# HDMI.net
KiCad netlist of a schematic drawn in Altium Designer
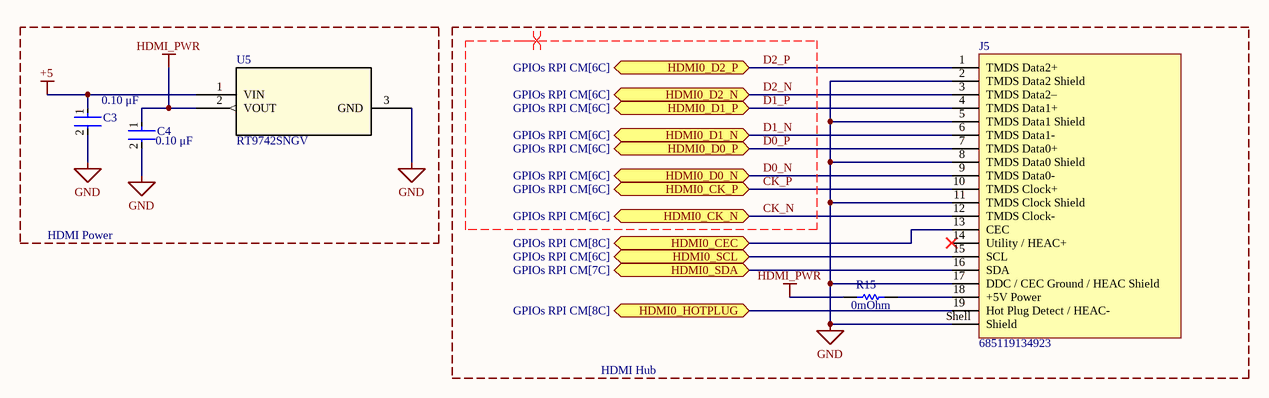
[diagram p0: HDMI.SchDoc]

(export (version "E")
  (design (tool "Eeschema 10.0.6"))
  (components
    (comp (ref "C3")
      (value "C0402C104K8PACTU")
      (footprint "FP-C0402-BB-MFG")
      (description "CAP CER 0.1UF 10V X5R 0402")
      (fields
        (field (name "CAPACITANCE") "0.10 μF")
        (field (name "MANUFACTURER") "Kemet")
        (field (name "TOLERANCE") "0.1")
      )
      (libsource (lib "Altium Content Vault") (part "b4654b650e69147ec39a6b967a45e02"))
    )
    (comp (ref "C4")
      (value "C0402C104K8PACTU")
      (footprint "FP-C0402-BB-MFG")
      (description "CAP CER 0.1UF 10V X5R 0402")
      (fields
        (field (name "CAPACITANCE") "0.10 μF")
        (field (name "MANUFACTURER") "Kemet")
        (field (name "TOLERANCE") "0.1")
      )
      (libsource (lib "Altium Content Vault") (part "b4654b650e69147ec39a6b967a45e02"))
    )
    (comp (ref "J5")
      (value "685119134923")
      (footprint "685119134923")
      (libsource (lib "Altium Content Vault") (part "HDMI_Type A"))
    )
    (comp (ref "R15")
      (value "ERJ2GE0R00X")
      (footprint "RESC1005X40X25LL05T05")
      (description "Chip Resistor, 0 Ohm, 0.1 W, -55 to 155 degC, 0402 (1005 Metric), RoHS, Tape and Reel")
      (fields
        (field (name "MANUFACTURER") "Panasonic")
        (field (name "RESISTANCE") "0mOhm")
        (field (name "TOLERANCE") "5%")
      )
      (libsource (lib "Altium Content Vault") (part "RES-2"))
    )
    (comp (ref "U5")
      (value "RT9742SNGV")
      (footprint "SOT_42SNGV_RIT")
      (description "HDMI Power")
      (libsource (lib "Compute Module 5 ") (part "RT9742SNGV"))
    )
  )
  (nets
    (net (code "1") (name "+5") (class "Default")
      (node (ref "C3") (pin "1") (pinfunction "1_1") (pintype "passive"))
      (node (ref "U5") (pin "1") (pinfunction "VIN_1") (pintype "passive"))
    )
    (net (code "2") (name "/CK_N") (class "Default")
      (node (ref "J5") (pin "12") (pinfunction "TMDS_Clock-_12") (pintype "passive"))
    )
    (net (code "3") (name "/CK_P") (class "Default")
      (node (ref "J5") (pin "10") (pinfunction "TMDS_Clock+_10") (pintype "passive"))
    )
    (net (code "4") (name "/D0_N") (class "Default")
      (node (ref "J5") (pin "9") (pinfunction "TMDS_Data0-_9") (pintype "passive"))
    )
    (net (code "5") (name "/D0_P") (class "Default")
      (node (ref "J5") (pin "7") (pinfunction "TMDS_Data0+_7") (pintype "passive"))
    )
    (net (code "6") (name "/D1_N") (class "Default")
      (node (ref "J5") (pin "6") (pinfunction "TMDS_Data1-_6") (pintype "passive"))
    )
    (net (code "7") (name "/D1_P") (class "Default")
      (node (ref "J5") (pin "4") (pinfunction "TMDS_Data1+_4") (pintype "passive"))
    )
    (net (code "8") (name "/D2_N") (class "Default")
      (node (ref "J5") (pin "3") (pinfunction "TMDS_Data2–_3") (pintype "passive"))
    )
    (net (code "9") (name "/D2_P") (class "Default")
      (node (ref "J5") (pin "1") (pinfunction "TMDS_Data2+_1") (pintype "passive"))
    )
    (net (code "10") (name "/HDMI0_CEC") (class "Default")
      (node (ref "J5") (pin "13") (pinfunction "CEC_13") (pintype "passive"))
    )
    (net (code "11") (name "/HDMI0_HOTPLUG") (class "Default")
      (node (ref "J5") (pin "19") (pinfunction "Hot_Plug_Detect_/_HEAC-_19") (pintype "passive"))
    )
    (net (code "12") (name "/HDMI0_SCL") (class "Default")
      (node (ref "J5") (pin "15") (pinfunction "SCL_15") (pintype "passive"))
    )
    (net (code "13") (name "/HDMI0_SDA") (class "Default")
      (node (ref "J5") (pin "16") (pinfunction "SDA_16") (pintype "passive"))
    )
    (net (code "14") (name "GND") (class "Default")
      (node (ref "C3") (pin "2") (pinfunction "2_2") (pintype "passive"))
      (node (ref "C4") (pin "2") (pinfunction "2_2") (pintype "passive"))
      (node (ref "J5") (pin "11") (pinfunction "TMDS_Clock_Shield_11") (pintype "passive"))
      (node (ref "J5") (pin "17") (pinfunction "DDC_/_CEC_Ground_/_HEAC_Shield_17") (pintype "passive"))
      (node (ref "J5") (pin "2") (pinfunction "TMDS_Data2_Shield_2") (pintype "passive"))
      (node (ref "J5") (pin "5") (pinfunction "TMDS_Data1_Shield_5") (pintype "passive"))
      (node (ref "J5") (pin "8") (pinfunction "TMDS_Data0_Shield_8") (pintype "passive"))
      (node (ref "J5") (pin "Shell") (pinfunction "Shield_Shell") (pintype "passive"))
      (node (ref "U5") (pin "3") (pinfunction "GND_3") (pintype "power_in"))
    )
    (net (code "15") (name "HDMI_PWR") (class "Default")
      (node (ref "C4") (pin "1") (pinfunction "1_1") (pintype "passive"))
      (node (ref "R15") (pin "1") (pinfunction "1_1") (pintype "passive"))
      (node (ref "U5") (pin "2") (pinfunction "VOUT_2") (pintype "output"))
    )
    (net (code "16") (name "Net-(J5-+5V_Power)") (class "Default")
      (node (ref "J5") (pin "18") (pinfunction "+5V_Power_18") (pintype "passive"))
      (node (ref "R15") (pin "2") (pinfunction "2_2") (pintype "passive"))
    )
    (net (code "17") (name "unconnected-(J5-Utility_{slash}_HEAC+-Pad14)") (class "Default")
      (node (ref "J5") (pin "14") (pinfunction "Utility_/_HEAC+_14") (pintype "passive+no_connect"))
    )
  )
)
